# 3V-Switcher-50mA.net
KiCad netlist of a schematic drawn in Altium Designer
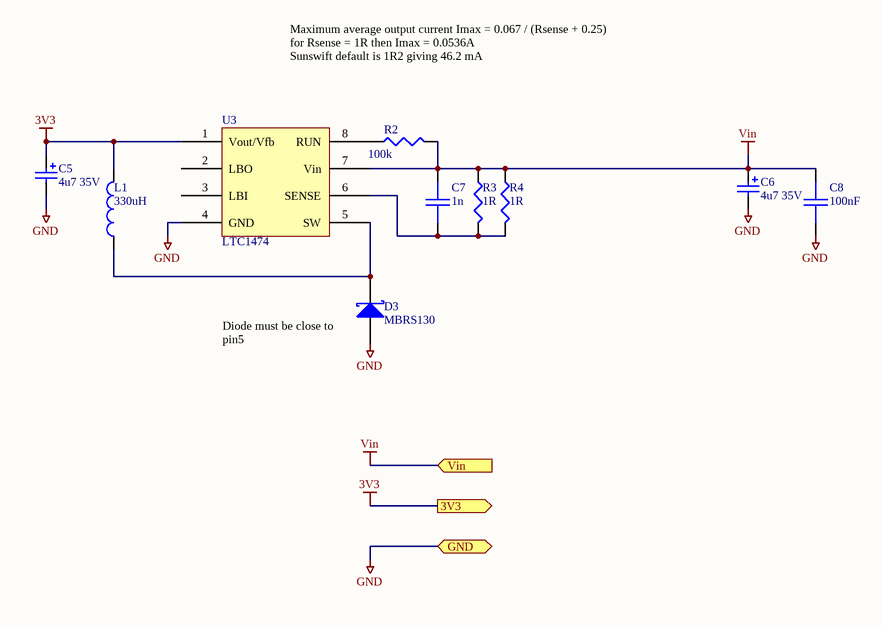
[diagram p0: 3V-Switcher-50mA.SCHDOC]

(export (version "E")
  (design (tool "Eeschema 10.0.6"))
  (components
    (comp (ref "C5")
      (value "4u7 35V")
      (footprint "MCCT-CASEC")
      (description "Polarized Capacitor (Surface Mount)")
      (libsource (lib "Miscellaneous Devices") (part "Cap Pol3"))
    )
    (comp (ref "C6")
      (value "4u7 35V")
      (footprint "MCCT-CASEC")
      (description "Polarized Capacitor (Surface Mount)")
      (libsource (lib "Miscellaneous Devices") (part "Cap Pol3"))
    )
    (comp (ref "C7")
      (value "1n")
      (footprint "0603")
      (description "Capacitor")
      (libsource (lib "Miscellaneous Devices") (part "CAP"))
    )
    (comp (ref "C8")
      (value "100nF")
      (footprint "0603")
      (description "Capacitor")
      (libsource (lib "Miscellaneous Devices") (part "CAP"))
    )
    (comp (ref "D3")
      (value "MBRS130")
      (footprint "SMB")
      (description "Schottky Diode")
      (libsource (lib "RCLDQ") (part "D SCHOTTKY"))
    )
    (comp (ref "L1")
      (value "330uH")
      (footprint "2220")
      (description "Inductor")
      (libsource (lib "Miscellaneous Devices") (part "Inductor"))
    )
    (comp (ref "R2")
      (value "100k")
      (footprint "0603")
      (description "Resistor")
      (libsource (lib "RCLDQ") (part "RES1"))
    )
    (comp (ref "R3")
      (value "1R")
      (footprint "0603")
      (description "Resistor")
      (libsource (lib "Miscellaneous Devices") (part "RES1"))
    )
    (comp (ref "R4")
      (value "1R")
      (footprint "0603")
      (description "Resistor")
      (libsource (lib "Miscellaneous Devices") (part "RES1"))
    )
    (comp (ref "U3")
      (value "LTC1474")
      (footprint "TSOP8")
      (description "Step-down converter")
      (libsource (lib "MiscellaneousIC") (part "LTC1474"))
    )
  )
  (nets
    (net (code "1") (name "3V3") (class "Default")
      (node (ref "C5") (pin "1") (pinfunction "1_1") (pintype "passive"))
      (node (ref "L1") (pin "2") (pinfunction "2_2") (pintype "passive"))
      (node (ref "U3") (pin "1") (pinfunction "Vout/Vfb_1") (pintype "passive"))
    )
    (net (code "2") (name "GND") (class "Default")
      (node (ref "C5") (pin "2") (pinfunction "2_2") (pintype "passive"))
      (node (ref "C6") (pin "2") (pinfunction "2_2") (pintype "passive"))
      (node (ref "C8") (pin "2") (pinfunction "2_2") (pintype "passive"))
      (node (ref "D3") (pin "A") (pinfunction "A_A") (pintype "passive"))
      (node (ref "U3") (pin "4") (pinfunction "GND_4") (pintype "passive"))
    )
    (net (code "3") (name "Net-(U3-RUN)") (class "Default")
      (node (ref "R2") (pin "1") (pinfunction "1_1") (pintype "passive"))
      (node (ref "U3") (pin "8") (pinfunction "RUN_8") (pintype "passive"))
    )
    (net (code "4") (name "Net-(U3-SENSE)") (class "Default")
      (node (ref "C7") (pin "2") (pinfunction "2_2") (pintype "passive"))
      (node (ref "R3") (pin "2") (pinfunction "2_2") (pintype "passive"))
      (node (ref "R4") (pin "2") (pinfunction "2_2") (pintype "passive"))
      (node (ref "U3") (pin "6") (pinfunction "SENSE_6") (pintype "passive"))
    )
    (net (code "5") (name "Net-(U3-SW)") (class "Default")
      (node (ref "D3") (pin "K") (pinfunction "K_K") (pintype "passive"))
      (node (ref "L1") (pin "1") (pinfunction "1_1") (pintype "passive"))
      (node (ref "U3") (pin "5") (pinfunction "SW_5") (pintype "passive"))
    )
    (net (code "6") (name "Vin") (class "Default")
      (node (ref "C6") (pin "1") (pinfunction "1_1") (pintype "passive"))
      (node (ref "C7") (pin "1") (pinfunction "1_1") (pintype "passive"))
      (node (ref "C8") (pin "1") (pinfunction "1_1") (pintype "passive"))
      (node (ref "R2") (pin "2") (pinfunction "2_2") (pintype "passive"))
      (node (ref "R3") (pin "1") (pinfunction "1_1") (pintype "passive"))
      (node (ref "R4") (pin "1") (pinfunction "1_1") (pintype "passive"))
      (node (ref "U3") (pin "7") (pinfunction "Vin_7") (pintype "passive"))
    )
    (net (code "7") (name "unconnected-(U3-LBI-Pad3)") (class "Default")
      (node (ref "U3") (pin "3") (pinfunction "LBI_3") (pintype "passive"))
    )
    (net (code "8") (name "unconnected-(U3-LBO-Pad2)") (class "Default")
      (node (ref "U3") (pin "2") (pinfunction "LBO_2") (pintype "passive"))
    )
  )
)
